# SWITCHBOARD.net
KiCad netlist of a schematic drawn in EAGLE
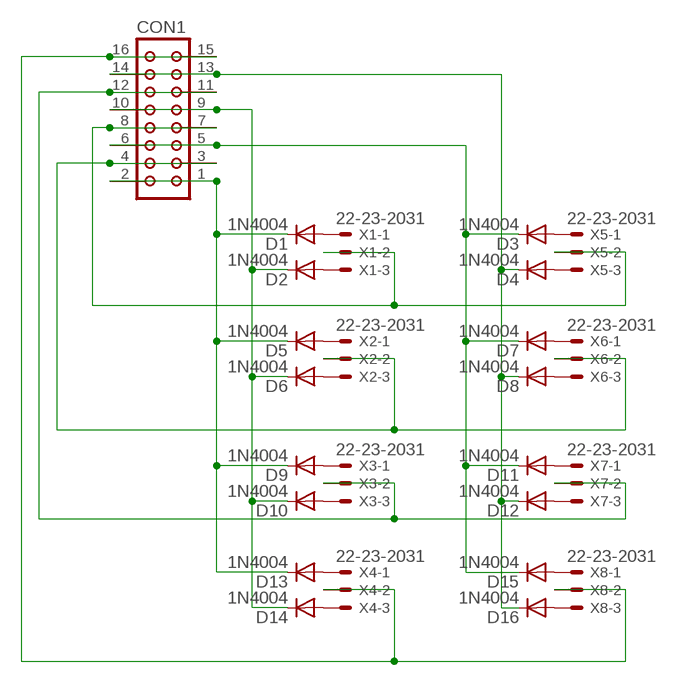
[diagram p0: schematic, sheet 1]

(export (version "E")
  (design (tool "Eeschema 10.0.6"))
  (components
    (comp (ref "CON1")
      (value "CON16")
      (footprint "eagle-import:CON16")
      (libsource (lib "eagle-import") (part "CON16"))
    )
    (comp (ref "D1")
      (value "1N4004")
      (footprint "eagle-import:DO41-10")
      (libsource (lib "eagle-import") (part "1N4004"))
    )
    (comp (ref "D2")
      (value "1N4004")
      (footprint "eagle-import:DO41-10")
      (libsource (lib "eagle-import") (part "1N4004"))
    )
    (comp (ref "D3")
      (value "1N4004")
      (footprint "eagle-import:DO41-10")
      (libsource (lib "eagle-import") (part "1N4004"))
    )
    (comp (ref "D4")
      (value "1N4004")
      (footprint "eagle-import:DO41-10")
      (libsource (lib "eagle-import") (part "1N4004"))
    )
    (comp (ref "D5")
      (value "1N4004")
      (footprint "eagle-import:DO41-10")
      (libsource (lib "eagle-import") (part "1N4004"))
    )
    (comp (ref "D6")
      (value "1N4004")
      (footprint "eagle-import:DO41-10")
      (libsource (lib "eagle-import") (part "1N4004"))
    )
    (comp (ref "D7")
      (value "1N4004")
      (footprint "eagle-import:DO41-10")
      (libsource (lib "eagle-import") (part "1N4004"))
    )
    (comp (ref "D8")
      (value "1N4004")
      (footprint "eagle-import:DO41-10")
      (libsource (lib "eagle-import") (part "1N4004"))
    )
    (comp (ref "D9")
      (value "1N4004")
      (footprint "eagle-import:DO41-10")
      (libsource (lib "eagle-import") (part "1N4004"))
    )
    (comp (ref "D10")
      (value "1N4004")
      (footprint "eagle-import:DO41-10")
      (libsource (lib "eagle-import") (part "1N4004"))
    )
    (comp (ref "D11")
      (value "1N4004")
      (footprint "eagle-import:DO41-10")
      (libsource (lib "eagle-import") (part "1N4004"))
    )
    (comp (ref "D12")
      (value "1N4004")
      (footprint "eagle-import:DO41-10")
      (libsource (lib "eagle-import") (part "1N4004"))
    )
    (comp (ref "D13")
      (value "1N4004")
      (footprint "eagle-import:DO41-10")
      (libsource (lib "eagle-import") (part "1N4004"))
    )
    (comp (ref "D14")
      (value "1N4004")
      (footprint "eagle-import:DO41-10")
      (libsource (lib "eagle-import") (part "1N4004"))
    )
    (comp (ref "D15")
      (value "1N4004")
      (footprint "eagle-import:DO41-10")
      (libsource (lib "eagle-import") (part "1N4004"))
    )
    (comp (ref "D16")
      (value "1N4004")
      (footprint "eagle-import:DO41-10")
      (libsource (lib "eagle-import") (part "1N4004"))
    )
    (comp (ref "X1")
      (value "22-23-2031")
      (footprint "eagle-import:22-23-2031")
      (fields (field (name "MF") "MOLEX"))
      (libsource (lib "eagle-import") (part "22-23-2031"))
    )
    (comp (ref "X2")
      (value "22-23-2031")
      (footprint "eagle-import:22-23-2031")
      (fields (field (name "MF") "MOLEX"))
      (libsource (lib "eagle-import") (part "22-23-2031"))
    )
    (comp (ref "X3")
      (value "22-23-2031")
      (footprint "eagle-import:22-23-2031")
      (fields (field (name "MF") "MOLEX"))
      (libsource (lib "eagle-import") (part "22-23-2031"))
    )
    (comp (ref "X4")
      (value "22-23-2031")
      (footprint "eagle-import:22-23-2031")
      (fields (field (name "MF") "MOLEX"))
      (libsource (lib "eagle-import") (part "22-23-2031"))
    )
    (comp (ref "X5")
      (value "22-23-2031")
      (footprint "eagle-import:22-23-2031")
      (fields (field (name "MF") "MOLEX"))
      (libsource (lib "eagle-import") (part "22-23-2031"))
    )
    (comp (ref "X6")
      (value "22-23-2031")
      (footprint "eagle-import:22-23-2031")
      (fields (field (name "MF") "MOLEX"))
      (libsource (lib "eagle-import") (part "22-23-2031"))
    )
    (comp (ref "X7")
      (value "22-23-2031")
      (footprint "eagle-import:22-23-2031")
      (fields (field (name "MF") "MOLEX"))
      (libsource (lib "eagle-import") (part "22-23-2031"))
    )
    (comp (ref "X8")
      (value "22-23-2031")
      (footprint "eagle-import:22-23-2031")
      (fields (field (name "MF") "MOLEX"))
      (libsource (lib "eagle-import") (part "22-23-2031"))
    )
  )
  (nets
    (net (code "1") (name "Net-(CON1-Pad1)") (class "Default")
      (node (ref "CON1") (pin "1") (pinfunction "1_1") (pintype "passive"))
      (node (ref "CON1") (pin "2") (pinfunction "2_2") (pintype "passive"))
      (node (ref "D1") (pin "C") (pinfunction "C_C") (pintype "passive"))
      (node (ref "D13") (pin "C") (pinfunction "C_C") (pintype "passive"))
      (node (ref "D5") (pin "C") (pinfunction "C_C") (pintype "passive"))
      (node (ref "D9") (pin "C") (pinfunction "C_C") (pintype "passive"))
    )
    (net (code "2") (name "Net-(CON1-Pad5)") (class "Default")
      (node (ref "CON1") (pin "5") (pinfunction "5_5") (pintype "passive"))
      (node (ref "CON1") (pin "6") (pinfunction "6_6") (pintype "passive"))
      (node (ref "D11") (pin "C") (pinfunction "C_C") (pintype "passive"))
      (node (ref "D15") (pin "C") (pinfunction "C_C") (pintype "passive"))
      (node (ref "D3") (pin "C") (pinfunction "C_C") (pintype "passive"))
      (node (ref "D7") (pin "C") (pinfunction "C_C") (pintype "passive"))
    )
    (net (code "3") (name "Net-(CON1-Pad10)") (class "Default")
      (node (ref "CON1") (pin "10") (pinfunction "10_10") (pintype "passive"))
      (node (ref "CON1") (pin "9") (pinfunction "9_9") (pintype "passive"))
      (node (ref "D10") (pin "C") (pinfunction "C_C") (pintype "passive"))
      (node (ref "D14") (pin "C") (pinfunction "C_C") (pintype "passive"))
      (node (ref "D2") (pin "C") (pinfunction "C_C") (pintype "passive"))
      (node (ref "D6") (pin "C") (pinfunction "C_C") (pintype "passive"))
    )
    (net (code "4") (name "Net-(CON1-Pad13)") (class "Default")
      (node (ref "CON1") (pin "13") (pinfunction "13_13") (pintype "passive"))
      (node (ref "CON1") (pin "14") (pinfunction "14_14") (pintype "passive"))
      (node (ref "D12") (pin "C") (pinfunction "C_C") (pintype "passive"))
      (node (ref "D16") (pin "C") (pinfunction "C_C") (pintype "passive"))
      (node (ref "D4") (pin "C") (pinfunction "C_C") (pintype "passive"))
      (node (ref "D8") (pin "C") (pinfunction "C_C") (pintype "passive"))
    )
    (net (code "5") (name "Net-(X1A-S)") (class "Default")
      (node (ref "D1") (pin "A") (pinfunction "A_A") (pintype "passive"))
      (node (ref "X1") (pin "1") (pinfunction "S_1") (pintype "passive"))
    )
    (net (code "6") (name "Net-(X1B-S)") (class "Default")
      (node (ref "CON1") (pin "7") (pinfunction "7_7") (pintype "passive"))
      (node (ref "CON1") (pin "8") (pinfunction "8_8") (pintype "passive"))
      (node (ref "X1") (pin "2") (pinfunction "S_2") (pintype "passive"))
      (node (ref "X5") (pin "2") (pinfunction "S_2") (pintype "passive"))
    )
    (net (code "7") (name "Net-(X1C-S)") (class "Default")
      (node (ref "D2") (pin "A") (pinfunction "A_A") (pintype "passive"))
      (node (ref "X1") (pin "3") (pinfunction "S_3") (pintype "passive"))
    )
    (net (code "8") (name "Net-(X2A-S)") (class "Default")
      (node (ref "D5") (pin "A") (pinfunction "A_A") (pintype "passive"))
      (node (ref "X2") (pin "1") (pinfunction "S_1") (pintype "passive"))
    )
    (net (code "9") (name "Net-(X2B-S)") (class "Default")
      (node (ref "CON1") (pin "3") (pinfunction "3_3") (pintype "passive"))
      (node (ref "CON1") (pin "4") (pinfunction "4_4") (pintype "passive"))
      (node (ref "X2") (pin "2") (pinfunction "S_2") (pintype "passive"))
      (node (ref "X6") (pin "2") (pinfunction "S_2") (pintype "passive"))
    )
    (net (code "10") (name "Net-(X2C-S)") (class "Default")
      (node (ref "D6") (pin "A") (pinfunction "A_A") (pintype "passive"))
      (node (ref "X2") (pin "3") (pinfunction "S_3") (pintype "passive"))
    )
    (net (code "11") (name "Net-(X3A-S)") (class "Default")
      (node (ref "D9") (pin "A") (pinfunction "A_A") (pintype "passive"))
      (node (ref "X3") (pin "1") (pinfunction "S_1") (pintype "passive"))
    )
    (net (code "12") (name "Net-(X3B-S)") (class "Default")
      (node (ref "CON1") (pin "11") (pinfunction "11_11") (pintype "passive"))
      (node (ref "CON1") (pin "12") (pinfunction "12_12") (pintype "passive"))
      (node (ref "X3") (pin "2") (pinfunction "S_2") (pintype "passive"))
      (node (ref "X7") (pin "2") (pinfunction "S_2") (pintype "passive"))
    )
    (net (code "13") (name "Net-(X3C-S)") (class "Default")
      (node (ref "D10") (pin "A") (pinfunction "A_A") (pintype "passive"))
      (node (ref "X3") (pin "3") (pinfunction "S_3") (pintype "passive"))
    )
    (net (code "14") (name "Net-(X4A-S)") (class "Default")
      (node (ref "D13") (pin "A") (pinfunction "A_A") (pintype "passive"))
      (node (ref "X4") (pin "1") (pinfunction "S_1") (pintype "passive"))
    )
    (net (code "15") (name "Net-(X4B-S)") (class "Default")
      (node (ref "CON1") (pin "15") (pinfunction "15_15") (pintype "passive"))
      (node (ref "CON1") (pin "16") (pinfunction "16_16") (pintype "passive"))
      (node (ref "X4") (pin "2") (pinfunction "S_2") (pintype "passive"))
      (node (ref "X8") (pin "2") (pinfunction "S_2") (pintype "passive"))
    )
    (net (code "16") (name "Net-(X4C-S)") (class "Default")
      (node (ref "D14") (pin "A") (pinfunction "A_A") (pintype "passive"))
      (node (ref "X4") (pin "3") (pinfunction "S_3") (pintype "passive"))
    )
    (net (code "17") (name "Net-(X5A-S)") (class "Default")
      (node (ref "D3") (pin "A") (pinfunction "A_A") (pintype "passive"))
      (node (ref "X5") (pin "1") (pinfunction "S_1") (pintype "passive"))
    )
    (net (code "18") (name "Net-(X5C-S)") (class "Default")
      (node (ref "D4") (pin "A") (pinfunction "A_A") (pintype "passive"))
      (node (ref "X5") (pin "3") (pinfunction "S_3") (pintype "passive"))
    )
    (net (code "19") (name "Net-(X6A-S)") (class "Default")
      (node (ref "D7") (pin "A") (pinfunction "A_A") (pintype "passive"))
      (node (ref "X6") (pin "1") (pinfunction "S_1") (pintype "passive"))
    )
    (net (code "20") (name "Net-(X6C-S)") (class "Default")
      (node (ref "D8") (pin "A") (pinfunction "A_A") (pintype "passive"))
      (node (ref "X6") (pin "3") (pinfunction "S_3") (pintype "passive"))
    )
    (net (code "21") (name "Net-(X7A-S)") (class "Default")
      (node (ref "D11") (pin "A") (pinfunction "A_A") (pintype "passive"))
      (node (ref "X7") (pin "1") (pinfunction "S_1") (pintype "passive"))
    )
    (net (code "22") (name "Net-(X7C-S)") (class "Default")
      (node (ref "D12") (pin "A") (pinfunction "A_A") (pintype "passive"))
      (node (ref "X7") (pin "3") (pinfunction "S_3") (pintype "passive"))
    )
    (net (code "23") (name "Net-(X8A-S)") (class "Default")
      (node (ref "D15") (pin "A") (pinfunction "A_A") (pintype "passive"))
      (node (ref "X8") (pin "1") (pinfunction "S_1") (pintype "passive"))
    )
    (net (code "24") (name "Net-(X8C-S)") (class "Default")
      (node (ref "D16") (pin "A") (pinfunction "A_A") (pintype "passive"))
      (node (ref "X8") (pin "3") (pinfunction "S_3") (pintype "passive"))
    )
  )
)
